# 220VAC_to_24VDC.net
KiCad netlist of a schematic drawn in Altium Designer
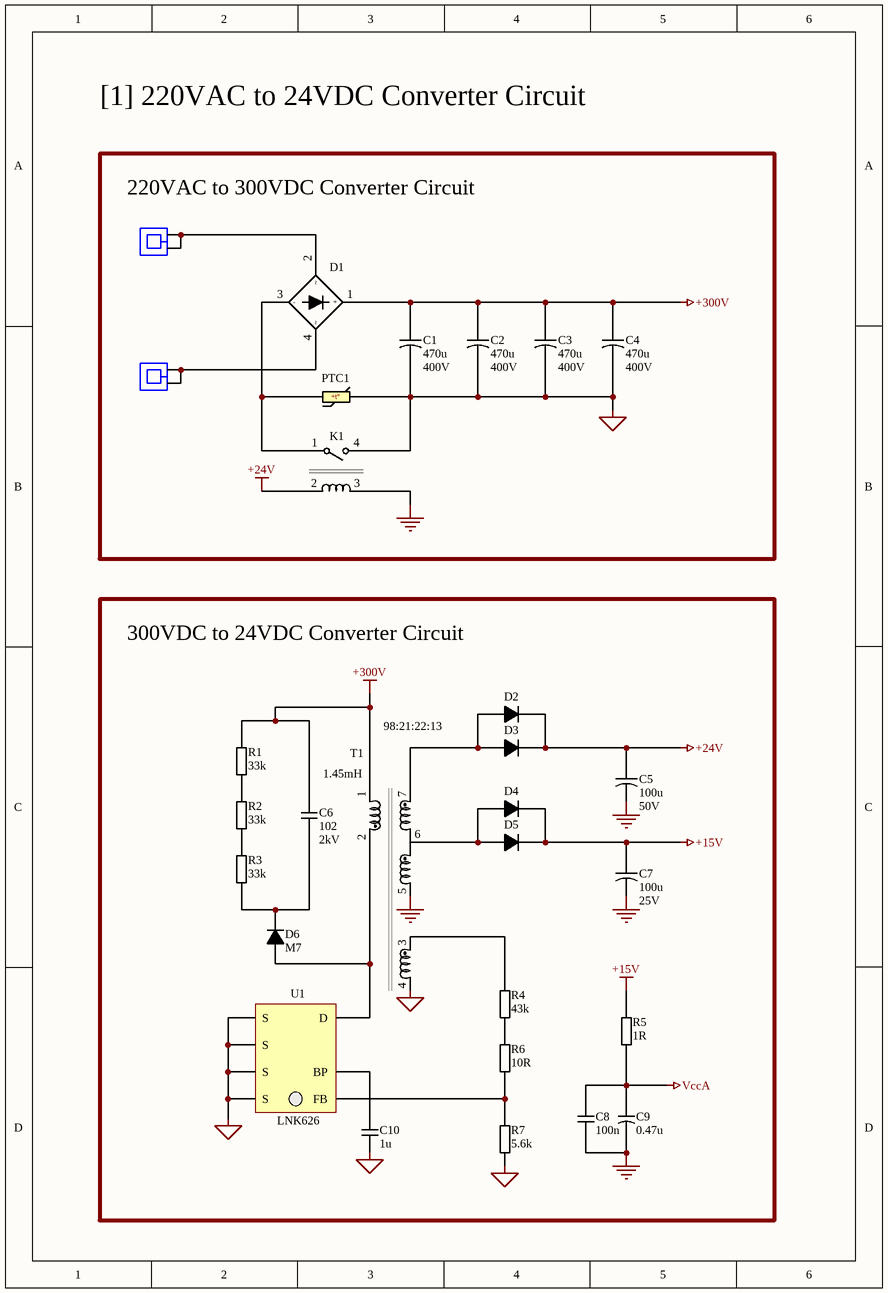
[diagram p0: 220VAC_to_24VDC.SchDoc]

(export (version "E")
  (design (tool "Eeschema 10.0.6"))
  (components
    (comp (ref "C1")
      (value "470u")
      (footprint "Cap_THD_Alum_10mm")
      (description "THD Aluminum Capacitor")
      (fields (field (name "VOLTAGE") "400V"))
      (libsource (lib "LamThach_Sch_Lib") (part "Cap_THD_Alum"))
    )
    (comp (ref "C2")
      (value "470u")
      (footprint "Cap_THD_Alum_10mm")
      (description "THD Aluminum Capacitor")
      (fields (field (name "VOLTAGE") "400V"))
      (libsource (lib "LamThach_Sch_Lib") (part "Cap_THD_Alum"))
    )
    (comp (ref "C3")
      (value "470u")
      (footprint "Cap_THD_Alum_10mm")
      (description "THD Aluminum Capacitor")
      (fields (field (name "VOLTAGE") "400V"))
      (libsource (lib "LamThach_Sch_Lib") (part "Cap_THD_Alum"))
    )
    (comp (ref "C4")
      (value "470u")
      (footprint "Cap_THD_Alum_10mm")
      (description "THD Aluminum Capacitor")
      (fields (field (name "VOLTAGE") "400V"))
      (libsource (lib "LamThach_Sch_Lib") (part "Cap_THD_Alum"))
    )
    (comp (ref "C5")
      (value "100u")
      (footprint "Cap_THD_Alum_2.5mm")
      (description "THD Aluminum Capacitor")
      (fields (field (name "VOLTAGE") "50V"))
      (libsource (lib "LamThach_Sch_Lib") (part "Cap_THD_Alum"))
    )
    (comp (ref "C6")
      (value "102")
      (footprint "Cap_THD_HVCeramic_5mm")
      (description "THD Ceramic Capacitor")
      (fields (field (name "VOLTAGE") "2kV"))
      (libsource (lib "LamThach_Sch_Lib") (part "Cap_THD_Ceramic"))
    )
    (comp (ref "C7")
      (value "100u")
      (footprint "Cap_THD_Alum_2.5mm")
      (description "THD Aluminum Capacitor")
      (fields (field (name "VOLTAGE") "25V"))
      (libsource (lib "LamThach_Sch_Lib") (part "Cap_THD_Alum"))
    )
    (comp (ref "C8")
      (value "100n")
      (footprint "Cap_SMD_0805")
      (description "0805 SMD Capacitor")
      (libsource (lib "LamThach_Sch_Lib") (part "Cap_SMD_0805"))
    )
    (comp (ref "C9")
      (value "0.47u")
      (footprint "Cap_THD_Tantalum_2.5mm")
      (fields (field (name "VOLTAGE") "V"))
      (libsource (lib "LamThach_Sch_Lib") (part "Cap_THD_Tantalum_2.5mm"))
    )
    (comp (ref "C10")
      (value "1u")
      (footprint "Cap_SMD_0805")
      (description "0805 SMD Capacitor")
      (libsource (lib "LamThach_Sch_Lib") (part "Cap_SMD_0805"))
    )
    (comp (ref "D1")
      (value "D")
      (footprint "Bridge_THD_14.3mm")
      (description "Full Wave Diode Bridge 1")
      (libsource (lib "LamThach_Sch_Lib") (part "Diode_Bridge_V1"))
    )
    (comp (ref "D2")
      (value "UF4007")
      (footprint "Diode_THD_10.8mm")
      (description "Rectifier Diode")
      (libsource (lib "LamThach_Sch_Lib") (part "Diode_Rectifier"))
    )
    (comp (ref "D3")
      (value "UF4007")
      (footprint "Diode_THD_10.8mm")
      (description "Rectifier Diode")
      (libsource (lib "LamThach_Sch_Lib") (part "Diode_Rectifier"))
    )
    (comp (ref "D4")
      (value "UF4007")
      (footprint "Diode_THD_10.8mm")
      (description "Rectifier Diode")
      (libsource (lib "LamThach_Sch_Lib") (part "Diode_Rectifier"))
    )
    (comp (ref "D5")
      (value "UF4007")
      (footprint "Diode_THD_10.8mm")
      (description "Rectifier Diode")
      (libsource (lib "LamThach_Sch_Lib") (part "Diode_Rectifier"))
    )
    (comp (ref "D6")
      (value "M7")
      (footprint "Diode_SMD_3.9mm")
      (description "Rectifier Diode")
      (libsource (lib "") (part "Diode_Rectifier_1"))
    )
    (comp (ref "J1")
      (value "63824-1")
      (footprint "CONN_QC_Faston_5mm")
      (description "Quick Connect Terminal")
      (fields (field (name "MANUFACTURER") "TE Connectivity"))
      (libsource (lib "LamThach_Sch_Lib") (part "CONN_QC_Faston"))
    )
    (comp (ref "J2")
      (value "63824-1")
      (footprint "CONN_QC_Faston_5mm")
      (description "Quick Connect Terminal")
      (fields (field (name "MANUFACTURER") "TE Connectivity"))
      (libsource (lib "LamThach_Sch_Lib") (part "CONN_QC_Faston"))
    )
    (comp (ref "K1")
      (value "K")
      (footprint "Relay_10mm")
      (libsource (lib "LamThach_Sch_Lib") (part "Relay_Generic_V2"))
    )
    (comp (ref "PTC1")
      (value "~")
      (footprint "PTC_THD_5mm")
      (description "PTC Inrush Current Limiters")
      (libsource (lib "LamThach_Sch_Lib") (part "ICL_PTC"))
    )
    (comp (ref "R1")
      (value "33k")
      (footprint "Res_SMD_0805")
      (description "SMD Resistor")
      (libsource (lib "LamThach_Sch_Lib") (part "Res_SMD"))
    )
    (comp (ref "R2")
      (value "33k")
      (footprint "Res_SMD_0805")
      (description "SMD Resistor")
      (libsource (lib "LamThach_Sch_Lib") (part "Res_SMD"))
    )
    (comp (ref "R3")
      (value "33k")
      (footprint "Res_SMD_0805")
      (description "SMD Resistor")
      (libsource (lib "LamThach_Sch_Lib") (part "Res_SMD"))
    )
    (comp (ref "R4")
      (value "43k")
      (footprint "Res_SMD_0805")
      (description "SMD Resistor")
      (libsource (lib "LamThach_Sch_Lib") (part "Res_SMD"))
    )
    (comp (ref "R5")
      (value "1R")
      (footprint "Res_SMD_2512")
      (description "SMD Resistor")
      (libsource (lib "LamThach_Sch_Lib") (part "Res_SMD"))
    )
    (comp (ref "R6")
      (value "10R")
      (footprint "Res_SMD_0805")
      (description "SMD Resistor")
      (libsource (lib "LamThach_Sch_Lib") (part "Res_SMD"))
    )
    (comp (ref "R7")
      (value "5.6k")
      (footprint "Res_SMD_0805")
      (description "SMD Resistor")
      (libsource (lib "LamThach_Sch_Lib") (part "Res_SMD"))
    )
    (comp (ref "T1")
      (value "1.45mH")
      (footprint "XFMR_BR22EEL_1179A")
      (description "98:21:22:13 Pulse Transformer")
      (fields (field (name "TURNS RATIO") "98:21:22:13"))
      (libsource (lib "LamThach_Sch_Lib") (part "XFMR_BR22EEL_1179A"))
    )
    (comp (ref "U1") (value "LNK626") (footprint "DIP8") (libsource (lib "LamThach_Sch_Lib") (part "LNK626")))
  )
  (nets
    (net (code "1") (name "+15V") (class "Default")
      (node (ref "C7") (pin "1") (pinfunction "+_1") (pintype "passive"))
      (node (ref "D4") (pin "2") (pinfunction "K_2") (pintype "passive"))
      (node (ref "D5") (pin "2") (pinfunction "K_2") (pintype "passive"))
      (node (ref "R5") (pin "1") (pinfunction "1_1") (pintype "passive"))
    )
    (net (code "2") (name "+24V") (class "Default")
      (node (ref "C5") (pin "1") (pinfunction "+_1") (pintype "passive"))
      (node (ref "D2") (pin "2") (pinfunction "K_2") (pintype "passive"))
      (node (ref "D3") (pin "2") (pinfunction "K_2") (pintype "passive"))
      (node (ref "K1") (pin "2") (pinfunction "Coil_1_2") (pintype "passive"))
    )
    (net (code "3") (name "+300V") (class "Default")
      (node (ref "C1") (pin "1") (pinfunction "+_1") (pintype "passive"))
      (node (ref "C2") (pin "1") (pinfunction "+_1") (pintype "passive"))
      (node (ref "C3") (pin "1") (pinfunction "+_1") (pintype "passive"))
      (node (ref "C4") (pin "1") (pinfunction "+_1") (pintype "passive"))
      (node (ref "C6") (pin "2") (pinfunction "2_2") (pintype "passive"))
      (node (ref "D1") (pin "1") (pinfunction "+_1") (pintype "passive"))
      (node (ref "R1") (pin "2") (pinfunction "2_2") (pintype "passive"))
      (node (ref "T1") (pin "1") (pinfunction "1_1") (pintype "passive"))
    )
    (net (code "4") (name "GND") (class "Default")
      (node (ref "C5") (pin "2") (pinfunction "-_2") (pintype "passive"))
      (node (ref "C7") (pin "2") (pinfunction "-_2") (pintype "passive"))
      (node (ref "C8") (pin "1") (pinfunction "1_1") (pintype "passive"))
      (node (ref "C9") (pin "2") (pinfunction "-_2") (pintype "passive"))
      (node (ref "K1") (pin "3") (pinfunction "Coil_2_3") (pintype "passive"))
      (node (ref "T1") (pin "5") (pinfunction "5_5") (pintype "passive"))
    )
    (net (code "5") (name "GND_1") (class "Default")
      (node (ref "C1") (pin "2") (pinfunction "-_2") (pintype "passive"))
      (node (ref "C10") (pin "1") (pinfunction "1_1") (pintype "passive"))
      (node (ref "C2") (pin "2") (pinfunction "-_2") (pintype "passive"))
      (node (ref "C3") (pin "2") (pinfunction "-_2") (pintype "passive"))
      (node (ref "C4") (pin "2") (pinfunction "-_2") (pintype "passive"))
      (node (ref "K1") (pin "4") (pinfunction "SW_2_4") (pintype "passive"))
      (node (ref "PTC1") (pin "2") (pinfunction "2_2") (pintype "passive"))
      (node (ref "R7") (pin "1") (pinfunction "1_1") (pintype "passive"))
      (node (ref "T1") (pin "4") (pinfunction "4_4") (pintype "passive"))
      (node (ref "U1") (pin "5") (pinfunction "S_5") (pintype "passive"))
      (node (ref "U1") (pin "6") (pinfunction "S_6") (pintype "passive"))
      (node (ref "U1") (pin "7") (pinfunction "S_7") (pintype "passive"))
      (node (ref "U1") (pin "8") (pinfunction "S_8") (pintype "passive"))
    )
    (net (code "6") (name "Net-(D1--)") (class "Default")
      (node (ref "D1") (pin "3") (pinfunction "-_3") (pintype "passive"))
      (node (ref "K1") (pin "1") (pinfunction "SW_1_1") (pintype "passive"))
      (node (ref "PTC1") (pin "1") (pinfunction "1_1") (pintype "passive"))
    )
    (net (code "7") (name "Net-(D1-~-Pad2)") (class "Default")
      (node (ref "D1") (pin "2") (pinfunction "~_2") (pintype "passive"))
      (node (ref "J1") (pin "1") (pinfunction "1_1") (pintype "passive"))
      (node (ref "J1") (pin "2") (pinfunction "2_2") (pintype "passive"))
    )
    (net (code "8") (name "Net-(D1-~-Pad4)") (class "Default")
      (node (ref "D1") (pin "4") (pinfunction "~_4") (pintype "passive"))
      (node (ref "J2") (pin "1") (pinfunction "1_1") (pintype "passive"))
      (node (ref "J2") (pin "2") (pinfunction "2_2") (pintype "passive"))
    )
    (net (code "9") (name "Net-(D2-A)") (class "Default")
      (node (ref "D2") (pin "1") (pinfunction "A_1") (pintype "passive"))
      (node (ref "D3") (pin "1") (pinfunction "A_1") (pintype "passive"))
      (node (ref "T1") (pin "7") (pinfunction "7_7") (pintype "passive"))
    )
    (net (code "10") (name "Net-(D4-A)") (class "Default")
      (node (ref "D4") (pin "1") (pinfunction "A_1") (pintype "passive"))
      (node (ref "D5") (pin "1") (pinfunction "A_1") (pintype "passive"))
      (node (ref "T1") (pin "6") (pinfunction "6_6") (pintype "passive"))
    )
    (net (code "11") (name "Net-(D6-A)") (class "Default")
      (node (ref "D6") (pin "2") (pinfunction "A_2") (pintype "passive"))
      (node (ref "T1") (pin "2") (pinfunction "2_2") (pintype "passive"))
      (node (ref "U1") (pin "4") (pinfunction "D_4") (pintype "passive"))
    )
    (net (code "12") (name "Net-(D6-K)") (class "Default")
      (node (ref "C6") (pin "1") (pinfunction "1_1") (pintype "passive"))
      (node (ref "D6") (pin "1") (pinfunction "K_1") (pintype "passive"))
      (node (ref "R3") (pin "1") (pinfunction "1_1") (pintype "passive"))
    )
    (net (code "13") (name "Net-(R1-Pad1)") (class "Default")
      (node (ref "R1") (pin "1") (pinfunction "1_1") (pintype "passive"))
      (node (ref "R2") (pin "2") (pinfunction "2_2") (pintype "passive"))
    )
    (net (code "14") (name "Net-(R2-Pad1)") (class "Default")
      (node (ref "R2") (pin "1") (pinfunction "1_1") (pintype "passive"))
      (node (ref "R3") (pin "2") (pinfunction "2_2") (pintype "passive"))
    )
    (net (code "15") (name "Net-(R4-Pad1)") (class "Default")
      (node (ref "R4") (pin "1") (pinfunction "1_1") (pintype "passive"))
      (node (ref "R6") (pin "2") (pinfunction "2_2") (pintype "passive"))
    )
    (net (code "16") (name "Net-(R4-Pad2)") (class "Default")
      (node (ref "R4") (pin "2") (pinfunction "2_2") (pintype "passive"))
      (node (ref "T1") (pin "3") (pinfunction "3_3") (pintype "passive"))
    )
    (net (code "17") (name "Net-(U1-BP)") (class "Default")
      (node (ref "C10") (pin "2") (pinfunction "2_2") (pintype "passive"))
      (node (ref "U1") (pin "2") (pinfunction "BP_2") (pintype "passive"))
    )
    (net (code "18") (name "Net-(U1-FB)") (class "Default")
      (node (ref "R6") (pin "1") (pinfunction "1_1") (pintype "passive"))
      (node (ref "R7") (pin "2") (pinfunction "2_2") (pintype "passive"))
      (node (ref "U1") (pin "1") (pinfunction "FB_1") (pintype "passive"))
    )
    (net (code "19") (name "VccA") (class "Default")
      (node (ref "C8") (pin "2") (pinfunction "2_2") (pintype "passive"))
      (node (ref "C9") (pin "1") (pinfunction "+_1") (pintype "passive"))
      (node (ref "R5") (pin "2") (pinfunction "2_2") (pintype "passive"))
    )
    (net (code "20") (name "unconnected-(U1-NC-Pad3)") (class "Default")
      (node (ref "U1") (pin "3") (pinfunction "NC_3") (pintype "passive"))
    )
  )
)
